# gatedriver_trafo_sma_compact_ACDC_ultra_.net
KiCad netlist of a schematic drawn in EAGLE
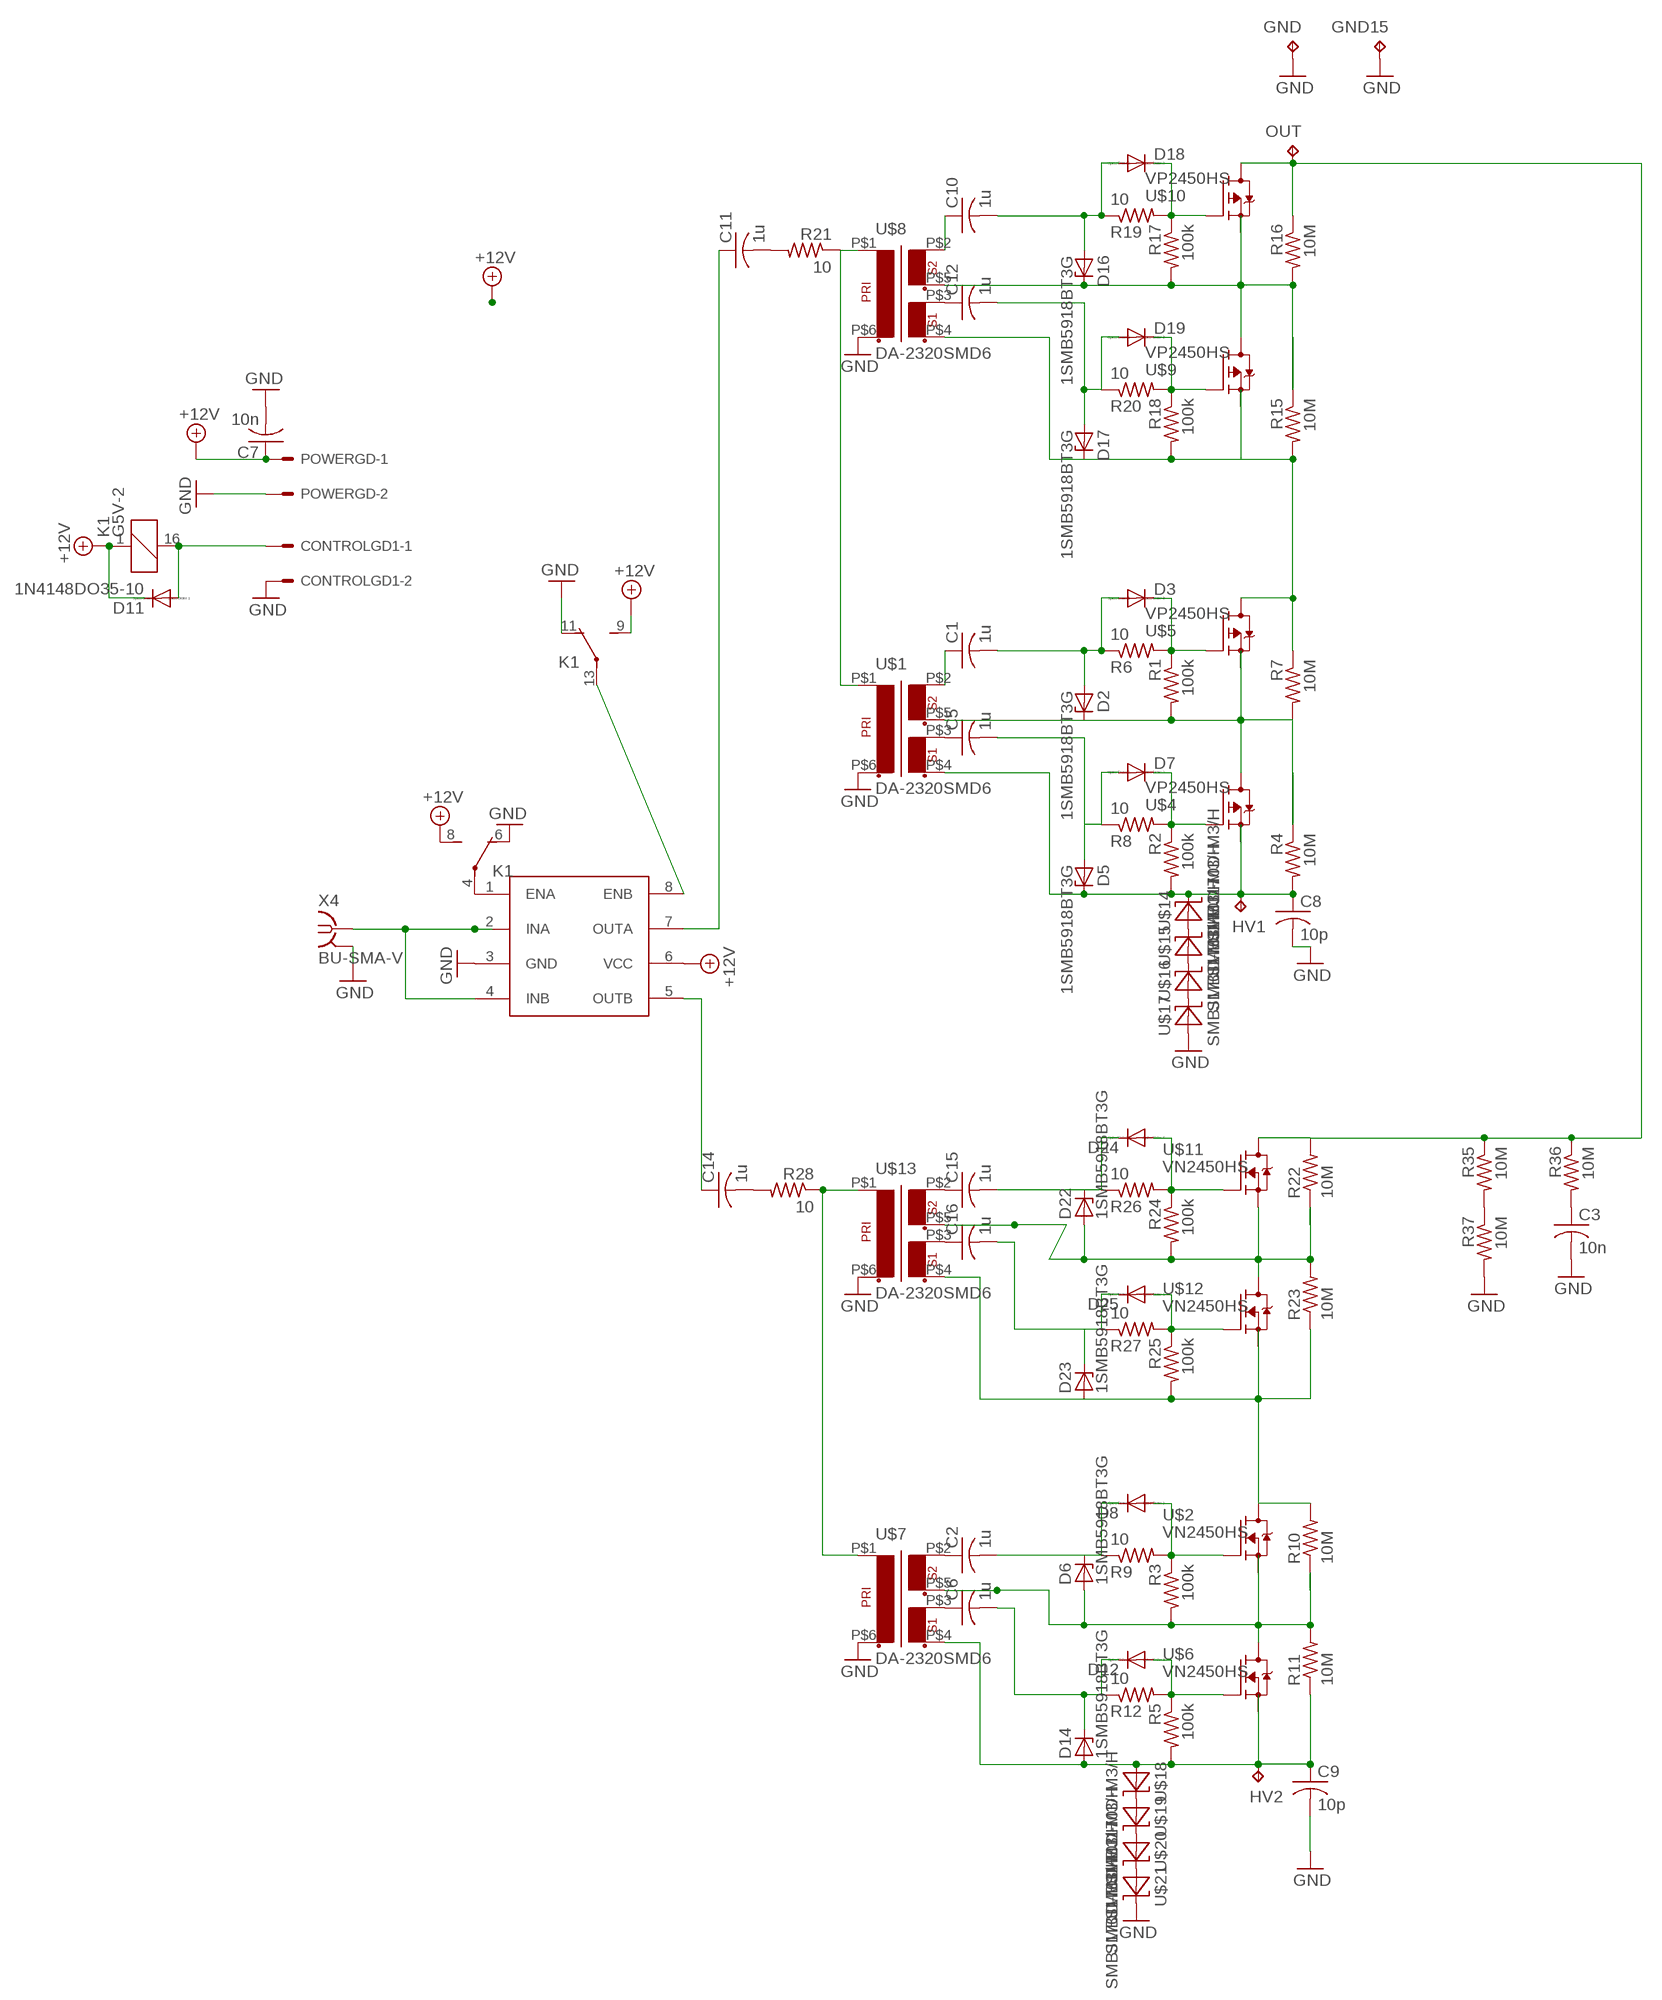
[diagram p0: schematic, sheet 1]

(export (version "E")
  (design (tool "Eeschema 10.0.6"))
  (components
    (comp (ref "C1")
      (value "1u")
      (footprint "eagle-import:C0805")
      (libsource (lib "eagle-import") (part "resistor_C-USC0805"))
    )
    (comp (ref "C2")
      (value "1u")
      (footprint "eagle-import:C0805")
      (libsource (lib "eagle-import") (part "resistor_C-USC0805"))
    )
    (comp (ref "C3")
      (value "10n")
      (footprint "eagle-import:C0805")
      (libsource (lib "eagle-import") (part "resistor_C-USC0805"))
    )
    (comp (ref "C5")
      (value "1u")
      (footprint "eagle-import:C0805")
      (libsource (lib "eagle-import") (part "resistor_C-USC0805"))
    )
    (comp (ref "C6")
      (value "1u")
      (footprint "eagle-import:C0805")
      (libsource (lib "eagle-import") (part "resistor_C-USC0805"))
    )
    (comp (ref "C7")
      (value "10n")
      (footprint "eagle-import:C050-030X075")
      (libsource (lib "eagle-import") (part "C-US050-030X075"))
    )
    (comp (ref "C8")
      (value "10p")
      (footprint "eagle-import:C102-064X133")
      (libsource (lib "eagle-import") (part "resistor_C-US102-064X133"))
    )
    (comp (ref "C9")
      (value "10p")
      (footprint "eagle-import:C102-064X133")
      (libsource (lib "eagle-import") (part "resistor_C-US102-064X133"))
    )
    (comp (ref "C10")
      (value "1u")
      (footprint "eagle-import:C0805")
      (libsource (lib "eagle-import") (part "resistor_C-USC0805"))
    )
    (comp (ref "C11")
      (value "1u")
      (footprint "eagle-import:C0805")
      (libsource (lib "eagle-import") (part "resistor_C-USC0805"))
    )
    (comp (ref "C12")
      (value "1u")
      (footprint "eagle-import:C0805")
      (libsource (lib "eagle-import") (part "resistor_C-USC0805"))
    )
    (comp (ref "C14")
      (value "1u")
      (footprint "eagle-import:C0805")
      (libsource (lib "eagle-import") (part "resistor_C-USC0805"))
    )
    (comp (ref "C15")
      (value "1u")
      (footprint "eagle-import:C0805")
      (libsource (lib "eagle-import") (part "resistor_C-USC0805"))
    )
    (comp (ref "C16")
      (value "1u")
      (footprint "eagle-import:C0805")
      (libsource (lib "eagle-import") (part "resistor_C-USC0805"))
    )
    (comp (ref "CONTROLGD1")
      (value "KK-156-2")
      (footprint "eagle-import:KK-156-2")
      (libsource (lib "eagle-import") (part "KK-156-2"))
    )
    (comp (ref "D2")
      (value "1SMB5918BT3G")
      (footprint "eagle-import:SMB")
      (libsource (lib "eagle-import") (part "ZENER-DIODESMB"))
    )
    (comp (ref "D3")
      (value "DIODE-SMB")
      (footprint "eagle-import:SMB")
      (libsource (lib "eagle-import") (part "DIODE-SMB"))
    )
    (comp (ref "D5")
      (value "1SMB5918BT3G")
      (footprint "eagle-import:SMB")
      (libsource (lib "eagle-import") (part "ZENER-DIODESMB"))
    )
    (comp (ref "D6")
      (value "1SMB5918BT3G")
      (footprint "eagle-import:SMB")
      (libsource (lib "eagle-import") (part "ZENER-DIODESMB"))
    )
    (comp (ref "D7")
      (value "DIODE-SMB")
      (footprint "eagle-import:SMB")
      (libsource (lib "eagle-import") (part "DIODE-SMB"))
    )
    (comp (ref "D8")
      (value "DIODE-SMB")
      (footprint "eagle-import:SMB")
      (libsource (lib "eagle-import") (part "DIODE-SMB"))
    )
    (comp (ref "D11")
      (value "1N4148DO35-10")
      (footprint "eagle-import:DO35-10")
      (libsource (lib "eagle-import") (part "1N4148DO35-10"))
    )
    (comp (ref "D12")
      (value "DIODE-SMB")
      (footprint "eagle-import:SMB")
      (libsource (lib "eagle-import") (part "DIODE-SMB"))
    )
    (comp (ref "D14")
      (value "1SMB5918BT3G")
      (footprint "eagle-import:SMB")
      (libsource (lib "eagle-import") (part "ZENER-DIODESMB"))
    )
    (comp (ref "D16")
      (value "1SMB5918BT3G")
      (footprint "eagle-import:SMB")
      (libsource (lib "eagle-import") (part "ZENER-DIODESMB"))
    )
    (comp (ref "D17")
      (value "1SMB5918BT3G")
      (footprint "eagle-import:SMB")
      (libsource (lib "eagle-import") (part "ZENER-DIODESMB"))
    )
    (comp (ref "D18")
      (value "DIODE-SMB")
      (footprint "eagle-import:SMB")
      (libsource (lib "eagle-import") (part "DIODE-SMB"))
    )
    (comp (ref "D19")
      (value "DIODE-SMB")
      (footprint "eagle-import:SMB")
      (libsource (lib "eagle-import") (part "DIODE-SMB"))
    )
    (comp (ref "D22")
      (value "1SMB5918BT3G")
      (footprint "eagle-import:SMB")
      (libsource (lib "eagle-import") (part "ZENER-DIODESMB"))
    )
    (comp (ref "D23")
      (value "1SMB5918BT3G")
      (footprint "eagle-import:SMB")
      (libsource (lib "eagle-import") (part "ZENER-DIODESMB"))
    )
    (comp (ref "D24")
      (value "DIODE-SMB")
      (footprint "eagle-import:SMB")
      (libsource (lib "eagle-import") (part "DIODE-SMB"))
    )
    (comp (ref "D25")
      (value "DIODE-SMB")
      (footprint "eagle-import:SMB")
      (libsource (lib "eagle-import") (part "DIODE-SMB"))
    )
    (comp (ref "GND")
      (value "TPPAD1-20Y")
      (footprint "eagle-import:P1-20Y")
      (libsource (lib "eagle-import") (part "TPPAD1-20Y"))
    )
    (comp (ref "GND15")
      (value "TPPAD1-20Y")
      (footprint "eagle-import:P1-20Y")
      (libsource (lib "eagle-import") (part "TPPAD1-20Y"))
    )
    (comp (ref "HV1")
      (value "TPPAD1-20Y")
      (footprint "eagle-import:P1-20Y")
      (libsource (lib "eagle-import") (part "TPPAD1-20Y"))
    )
    (comp (ref "HV2")
      (value "TPPAD1-20Y")
      (footprint "eagle-import:P1-20Y")
      (libsource (lib "eagle-import") (part "TPPAD1-20Y"))
    )
    (comp (ref "K1")
      (value "G5V-2")
      (footprint "eagle-import:G5V-2")
      (fields (field (name "MPN") "G5V-2 5DC"))
      (libsource (lib "eagle-import") (part "G5V-2"))
    )
    (comp (ref "OUT")
      (value "TPPAD1-20Y")
      (footprint "eagle-import:P1-20Y")
      (libsource (lib "eagle-import") (part "TPPAD1-20Y"))
    )
    (comp (ref "POWERGD")
      (value "KK-156-2")
      (footprint "eagle-import:KK-156-2")
      (libsource (lib "eagle-import") (part "KK-156-2"))
    )
    (comp (ref "R1")
      (value "100k")
      (footprint "eagle-import:R0805")
      (libsource (lib "eagle-import") (part "R-US_R0805"))
    )
    (comp (ref "R2")
      (value "100k")
      (footprint "eagle-import:R0805")
      (libsource (lib "eagle-import") (part "R-US_R0805"))
    )
    (comp (ref "R3")
      (value "100k")
      (footprint "eagle-import:R0805")
      (libsource (lib "eagle-import") (part "R-US_R0805"))
    )
    (comp (ref "R4")
      (value "10M")
      (footprint "eagle-import:R2512")
      (libsource (lib "eagle-import") (part "R-US_R2512"))
    )
    (comp (ref "R5")
      (value "100k")
      (footprint "eagle-import:R0805")
      (libsource (lib "eagle-import") (part "R-US_R0805"))
    )
    (comp (ref "R6")
      (value "10")
      (footprint "eagle-import:R0805")
      (libsource (lib "eagle-import") (part "R-US_R0805"))
    )
    (comp (ref "R7")
      (value "10M")
      (footprint "eagle-import:R2512")
      (libsource (lib "eagle-import") (part "R-US_R2512"))
    )
    (comp (ref "R8")
      (value "10")
      (footprint "eagle-import:R0805")
      (libsource (lib "eagle-import") (part "R-US_R0805"))
    )
    (comp (ref "R9")
      (value "10")
      (footprint "eagle-import:R0805")
      (libsource (lib "eagle-import") (part "R-US_R0805"))
    )
    (comp (ref "R10")
      (value "10M")
      (footprint "eagle-import:R2512")
      (libsource (lib "eagle-import") (part "R-US_R2512"))
    )
    (comp (ref "R11")
      (value "10M")
      (footprint "eagle-import:R2512")
      (libsource (lib "eagle-import") (part "R-US_R2512"))
    )
    (comp (ref "R12")
      (value "10")
      (footprint "eagle-import:R0805")
      (libsource (lib "eagle-import") (part "R-US_R0805"))
    )
    (comp (ref "R15")
      (value "10M")
      (footprint "eagle-import:R2512")
      (libsource (lib "eagle-import") (part "R-US_R2512"))
    )
    (comp (ref "R16")
      (value "10M")
      (footprint "eagle-import:R2512")
      (libsource (lib "eagle-import") (part "R-US_R2512"))
    )
    (comp (ref "R17")
      (value "100k")
      (footprint "eagle-import:R0805")
      (libsource (lib "eagle-import") (part "R-US_R0805"))
    )
    (comp (ref "R18")
      (value "100k")
      (footprint "eagle-import:R0805")
      (libsource (lib "eagle-import") (part "R-US_R0805"))
    )
    (comp (ref "R19")
      (value "10")
      (footprint "eagle-import:R0805")
      (libsource (lib "eagle-import") (part "R-US_R0805"))
    )
    (comp (ref "R20")
      (value "10")
      (footprint "eagle-import:R0805")
      (libsource (lib "eagle-import") (part "R-US_R0805"))
    )
    (comp (ref "R21")
      (value "10")
      (footprint "eagle-import:R0805")
      (libsource (lib "eagle-import") (part "R-US_R0805"))
    )
    (comp (ref "R22")
      (value "10M")
      (footprint "eagle-import:R2512")
      (libsource (lib "eagle-import") (part "R-US_R2512"))
    )
    (comp (ref "R23")
      (value "10M")
      (footprint "eagle-import:R2512")
      (libsource (lib "eagle-import") (part "R-US_R2512"))
    )
    (comp (ref "R24")
      (value "100k")
      (footprint "eagle-import:R0805")
      (libsource (lib "eagle-import") (part "R-US_R0805"))
    )
    (comp (ref "R25")
      (value "100k")
      (footprint "eagle-import:R0805")
      (libsource (lib "eagle-import") (part "R-US_R0805"))
    )
    (comp (ref "R26")
      (value "10")
      (footprint "eagle-import:R0805")
      (libsource (lib "eagle-import") (part "R-US_R0805"))
    )
    (comp (ref "R27")
      (value "10")
      (footprint "eagle-import:R0805")
      (libsource (lib "eagle-import") (part "R-US_R0805"))
    )
    (comp (ref "R28")
      (value "10")
      (footprint "eagle-import:R0805")
      (libsource (lib "eagle-import") (part "R-US_R0805"))
    )
    (comp (ref "R35")
      (value "10M")
      (footprint "eagle-import:R2512")
      (libsource (lib "eagle-import") (part "R-US_R2512"))
    )
    (comp (ref "R36")
      (value "10M")
      (footprint "eagle-import:R2512")
      (libsource (lib "eagle-import") (part "R-US_R2512"))
    )
    (comp (ref "R37")
      (value "10M")
      (footprint "eagle-import:R2512")
      (libsource (lib "eagle-import") (part "R-US_R2512"))
    )
    (comp (ref "U$1")
      (value "DA-2320SMD6")
      (footprint "eagle-import:SMD6")
      (libsource (lib "eagle-import") (part "DA-2320SMD6"))
    )
    (comp (ref "U$2")
      (value "VN2450HS")
      (footprint "eagle-import:SO89_HS")
      (libsource (lib "eagle-import") (part "VN2450HS"))
    )
    (comp (ref "U$3")
      (value "UCC27425")
      (footprint "eagle-import:DIL08")
      (libsource (lib "eagle-import") (part "UCC27425"))
    )
    (comp (ref "U$4")
      (value "VP2450HS")
      (footprint "eagle-import:SO89_HS")
      (libsource (lib "eagle-import") (part "VP2450HS"))
    )
    (comp (ref "U$5")
      (value "VP2450HS")
      (footprint "eagle-import:SO89_HS")
      (libsource (lib "eagle-import") (part "VP2450HS"))
    )
    (comp (ref "U$6")
      (value "VN2450HS")
      (footprint "eagle-import:SO89_HS")
      (libsource (lib "eagle-import") (part "VN2450HS"))
    )
    (comp (ref "U$7")
      (value "DA-2320SMD6")
      (footprint "eagle-import:SMD6")
      (libsource (lib "eagle-import") (part "DA-2320SMD6"))
    )
    (comp (ref "U$8")
      (value "DA-2320SMD6")
      (footprint "eagle-import:SMD6")
      (libsource (lib "eagle-import") (part "DA-2320SMD6"))
    )
    (comp (ref "U$9")
      (value "VP2450HS")
      (footprint "eagle-import:SO89_HS")
      (libsource (lib "eagle-import") (part "VP2450HS"))
    )
    (comp (ref "U$10")
      (value "VP2450HS")
      (footprint "eagle-import:SO89_HS")
      (libsource (lib "eagle-import") (part "VP2450HS"))
    )
    (comp (ref "U$11")
      (value "VN2450HS")
      (footprint "eagle-import:SO89_HS")
      (libsource (lib "eagle-import") (part "VN2450HS"))
    )
    (comp (ref "U$12")
      (value "VN2450HS")
      (footprint "eagle-import:SO89_HS")
      (libsource (lib "eagle-import") (part "VN2450HS"))
    )
    (comp (ref "U$13")
      (value "DA-2320SMD6")
      (footprint "eagle-import:SMD6")
      (libsource (lib "eagle-import") (part "DA-2320SMD6"))
    )
    (comp (ref "U$14")
      (value "SMBJ170D-M3/H")
      (footprint "eagle-import:DO214AA")
      (libsource (lib "eagle-import") (part "SMBJ170D-M3/H"))
    )
    (comp (ref "U$15")
      (value "SMBJ170D-M3/H")
      (footprint "eagle-import:DO214AA")
      (libsource (lib "eagle-import") (part "SMBJ170D-M3/H"))
    )
    (comp (ref "U$16")
      (value "SMBJ170D-M3/H")
      (footprint "eagle-import:DO214AA")
      (libsource (lib "eagle-import") (part "SMBJ170D-M3/H"))
    )
    (comp (ref "U$17")
      (value "SMBJ170D-M3/H")
      (footprint "eagle-import:DO214AA")
      (libsource (lib "eagle-import") (part "SMBJ170D-M3/H"))
    )
    (comp (ref "U$18")
      (value "SMBJ170D-M3/H")
      (footprint "eagle-import:DO214AA")
      (libsource (lib "eagle-import") (part "SMBJ170D-M3/H"))
    )
    (comp (ref "U$19")
      (value "SMBJ170D-M3/H")
      (footprint "eagle-import:DO214AA")
      (libsource (lib "eagle-import") (part "SMBJ170D-M3/H"))
    )
    (comp (ref "U$20")
      (value "SMBJ170D-M3/H")
      (footprint "eagle-import:DO214AA")
      (libsource (lib "eagle-import") (part "SMBJ170D-M3/H"))
    )
    (comp (ref "U$21")
      (value "SMBJ170D-M3/H")
      (footprint "eagle-import:DO214AA")
      (libsource (lib "eagle-import") (part "SMBJ170D-M3/H"))
    )
    (comp (ref "X4")
      (value "BU-SMA-V")
      (footprint "eagle-import:BU-SMA-V")
      (libsource (lib "eagle-import") (part "BU-SMA-V"))
    )
  )
  (nets
    (net (code "1") (name "+12V") (class "Default")
      (node (ref "C7") (pin "1") (pinfunction "1_1") (pintype "passive"))
      (node (ref "D11") (pin "C") (pinfunction "C_C") (pintype "passive"))
      (node (ref "K1") (pin "1") (pinfunction "1_1") (pintype "passive"))
      (node (ref "K1") (pin "8") (pinfunction "S_8") (pintype "passive"))
      (node (ref "K1") (pin "9") (pinfunction "S_9") (pintype "passive"))
      (node (ref "POWERGD") (pin "1") (pinfunction "S_1") (pintype "passive"))
      (node (ref "U$3") (pin "6") (pinfunction "VCC_6") (pintype "bidirectional"))
    )
    (net (code "2") (name "GND") (class "Default")
      (node (ref "C3") (pin "2") (pinfunction "2_2") (pintype "passive"))
      (node (ref "C7") (pin "2") (pinfunction "2_2") (pintype "passive"))
      (node (ref "C8") (pin "2") (pinfunction "2_2") (pintype "passive"))
      (node (ref "C9") (pin "2") (pinfunction "2_2") (pintype "passive"))
      (node (ref "CONTROLGD1") (pin "2") (pinfunction "S_2") (pintype "passive"))
      (node (ref "GND") (pin "TP") (pinfunction "TP_TP") (pintype "input"))
      (node (ref "GND15") (pin "TP") (pinfunction "TP_TP") (pintype "input"))
      (node (ref "K1") (pin "11") (pinfunction "O_11") (pintype "passive"))
      (node (ref "K1") (pin "6") (pinfunction "O_6") (pintype "passive"))
      (node (ref "POWERGD") (pin "2") (pinfunction "S_2") (pintype "passive"))
      (node (ref "R37") (pin "2") (pinfunction "2_2") (pintype "passive"))
      (node (ref "U$1") (pin "P$6") (pinfunction "2_P$6") (pintype "passive"))
      (node (ref "U$13") (pin "P$6") (pinfunction "2_P$6") (pintype "passive"))
      (node (ref "U$17") (pin "A") (pinfunction "A_A") (pintype "passive"))
      (node (ref "U$21") (pin "C") (pinfunction "C_C") (pintype "passive"))
      (node (ref "U$3") (pin "3") (pinfunction "GND_3") (pintype "bidirectional"))
      (node (ref "U$7") (pin "P$6") (pinfunction "2_P$6") (pintype "passive"))
      (node (ref "U$8") (pin "P$6") (pinfunction "2_P$6") (pintype "passive"))
      (node (ref "X4") (pin "2") (pinfunction "2_2") (pintype "passive"))
      (node (ref "X4") (pin "3") (pinfunction "2_3") (pintype "passive"))
      (node (ref "X4") (pin "4") (pinfunction "2_4") (pintype "passive"))
      (node (ref "X4") (pin "5") (pinfunction "2_5") (pintype "passive"))
    )
    (net (code "3") (name "Net-(C1-Pad2)") (class "Default")
      (node (ref "C1") (pin "2") (pinfunction "2_2") (pintype "passive"))
      (node (ref "D2") (pin "A") (pinfunction "A_A") (pintype "passive"))
      (node (ref "D3") (pin "A") (pinfunction "A_A") (pintype "passive"))
      (node (ref "R6") (pin "1") (pinfunction "1_1") (pintype "passive"))
    )
    (net (code "4") (name "Net-(C2-Pad2)") (class "Default")
      (node (ref "C2") (pin "2") (pinfunction "2_2") (pintype "passive"))
      (node (ref "D6") (pin "C") (pinfunction "C_C") (pintype "passive"))
      (node (ref "D8") (pin "C") (pinfunction "C_C") (pintype "passive"))
      (node (ref "R9") (pin "1") (pinfunction "1_1") (pintype "passive"))
    )
    (net (code "5") (name "Net-(C3-Pad1)") (class "Default")
      (node (ref "C3") (pin "1") (pinfunction "1_1") (pintype "passive"))
      (node (ref "R36") (pin "2") (pinfunction "2_2") (pintype "passive"))
    )
    (net (code "6") (name "Net-(C5-Pad2)") (class "Default")
      (node (ref "C5") (pin "2") (pinfunction "2_2") (pintype "passive"))
      (node (ref "D5") (pin "A") (pinfunction "A_A") (pintype "passive"))
      (node (ref "D7") (pin "A") (pinfunction "A_A") (pintype "passive"))
      (node (ref "R8") (pin "1") (pinfunction "1_1") (pintype "passive"))
    )
    (net (code "7") (name "Net-(C6-Pad2)") (class "Default")
      (node (ref "C6") (pin "2") (pinfunction "2_2") (pintype "passive"))
      (node (ref "D12") (pin "C") (pinfunction "C_C") (pintype "passive"))
      (node (ref "D14") (pin "C") (pinfunction "C_C") (pintype "passive"))
      (node (ref "R12") (pin "1") (pinfunction "1_1") (pintype "passive"))
    )
    (net (code "8") (name "Net-(C10-Pad2)") (class "Default")
      (node (ref "C10") (pin "2") (pinfunction "2_2") (pintype "passive"))
      (node (ref "D16") (pin "A") (pinfunction "A_A") (pintype "passive"))
      (node (ref "D18") (pin "A") (pinfunction "A_A") (pintype "passive"))
      (node (ref "R19") (pin "1") (pinfunction "1_1") (pintype "passive"))
    )
    (net (code "9") (name "Net-(C11-Pad2)") (class "Default")
      (node (ref "C11") (pin "2") (pinfunction "2_2") (pintype "passive"))
      (node (ref "R21") (pin "2") (pinfunction "2_2") (pintype "passive"))
    )
    (net (code "10") (name "Net-(C12-Pad2)") (class "Default")
      (node (ref "C12") (pin "2") (pinfunction "2_2") (pintype "passive"))
      (node (ref "D17") (pin "A") (pinfunction "A_A") (pintype "passive"))
      (node (ref "D19") (pin "A") (pinfunction "A_A") (pintype "passive"))
      (node (ref "R20") (pin "1") (pinfunction "1_1") (pintype "passive"))
    )
    (net (code "11") (name "Net-(C14-Pad2)") (class "Default")
      (node (ref "C14") (pin "2") (pinfunction "2_2") (pintype "passive"))
      (node (ref "R28") (pin "2") (pinfunction "2_2") (pintype "passive"))
    )
    (net (code "12") (name "Net-(C15-Pad2)") (class "Default")
      (node (ref "C15") (pin "2") (pinfunction "2_2") (pintype "passive"))
      (node (ref "D22") (pin "C") (pinfunction "C_C") (pintype "passive"))
      (node (ref "D24") (pin "C") (pinfunction "C_C") (pintype "passive"))
      (node (ref "R26") (pin "1") (pinfunction "1_1") (pintype "passive"))
    )
    (net (code "13") (name "Net-(C16-Pad2)") (class "Default")
      (node (ref "C16") (pin "2") (pinfunction "2_2") (pintype "passive"))
      (node (ref "D23") (pin "C") (pinfunction "C_C") (pintype "passive"))
      (node (ref "D25") (pin "C") (pinfunction "C_C") (pintype "passive"))
      (node (ref "R27") (pin "1") (pinfunction "1_1") (pintype "passive"))
    )
    (net (code "14") (name "Net-(CONTROLGD1A-S)") (class "Default")
      (node (ref "CONTROLGD1") (pin "1") (pinfunction "S_1") (pintype "passive"))
      (node (ref "D11") (pin "A") (pinfunction "A_A") (pintype "passive"))
      (node (ref "K1") (pin "16") (pinfunction "2_16") (pintype "passive"))
    )
    (net (code "15") (name "Net-(K1A-P)") (class "Default")
      (node (ref "K1") (pin "4") (pinfunction "P_4") (pintype "passive"))
      (node (ref "U$3") (pin "1") (pinfunction "ENA_1") (pintype "bidirectional"))
    )
    (net (code "16") (name "Net-(K1B-P)") (class "Default")
      (node (ref "K1") (pin "13") (pinfunction "P_13") (pintype "passive"))
      (node (ref "U$3") (pin "8") (pinfunction "ENB_8") (pintype "bidirectional"))
    )
    (net (code "17") (name "Net-(OUT-PadTP)") (class "Default")
      (node (ref "OUT") (pin "TP") (pinfunction "TP_TP") (pintype "input"))
      (node (ref "R16") (pin "1") (pinfunction "1_1") (pintype "passive"))
      (node (ref "R22") (pin "2") (pinfunction "2_2") (pintype "passive"))
      (node (ref "R35") (pin "1") (pinfunction "1_1") (pintype "passive"))
      (node (ref "R36") (pin "1") (pinfunction "1_1") (pintype "passive"))
      (node (ref "U$10") (pin "C") (pinfunction "D_C") (pintype "passive"))
      (node (ref "U$10") (pin "C@1") (pinfunction "D_C@1") (pintype "passive"))
      (node (ref "U$11") (pin "C") (pinfunction "D_C") (pintype "passive"))
      (node (ref "U$11") (pin "C@1") (pinfunction "D_C@1") (pintype "passive"))
    )
    (net (code "18") (name "Net-(R35-Pad2)") (class "Default")
      (node (ref "R35") (pin "2") (pinfunction "2_2") (pintype "passive"))
      (node (ref "R37") (pin "1") (pinfunction "1_1") (pintype "passive"))
    )
    (net (code "19") (name "Net-(U$1-1)") (class "Default")
      (node (ref "R21") (pin "1") (pinfunction "1_1") (pintype "passive"))
      (node (ref "U$1") (pin "P$1") (pinfunction "1_P$1") (pintype "passive"))
      (node (ref "U$8") (pin "P$1") (pinfunction "1_P$1") (pintype "passive"))
    )
    (net (code "20") (name "Net-(U$1-3)") (class "Default")
      (node (ref "C8") (pin "1") (pinfunction "1_1") (pintype "passive"))
      (node (ref "D5") (pin "C") (pinfunction "C_C") (pintype "passive"))
      (node (ref "HV1") (pin "TP") (pinfunction "TP_TP") (pintype "input"))
      (node (ref "R2") (pin "2") (pinfunction "2_2") (pintype "passive"))
      (node (ref "R4") (pin "2") (pinfunction "2_2") (pintype "passive"))
      (node (ref "U$1") (pin "P$4") (pinfunction "3_P$4") (pintype "passive"))
      (node (ref "U$14") (pin "C") (pinfunction "C_C") (pintype "passive"))
      (node (ref "U$4") (pin "E") (pinfunction "S_E") (pintype "passive"))
    )
    (net (code "21") (name "Net-(U$1-4)") (class "Default")
      (node (ref "C5") (pin "1") (pinfunction "1_1") (pintype "passive"))
      (node (ref "U$1") (pin "P$3") (pinfunction "4_P$3") (pintype "passive"))
    )
    (net (code "22") (name "Net-(U$1-5)") (class "Default")
      (node (ref "D2") (pin "C") (pinfunction "C_C") (pintype "passive"))
      (node (ref "R1") (pin "2") (pinfunction "2_2") (pintype "passive"))
      (node (ref "R4") (pin "1") (pinfunction "1_1") (pintype "passive"))
      (node (ref "R7") (pin "2") (pinfunction "2_2") (pintype "passive"))
      (node (ref "U$1") (pin "P$5") (pinfunction "5_P$5") (pintype "passive"))
      (node (ref "U$4") (pin "C") (pinfunction "D_C") (pintype "passive"))
      (node (ref "U$4") (pin "C@1") (pinfunction "D_C@1") (pintype "passive"))
      (node (ref "U$5") (pin "E") (pinfunction "S_E") (pintype "passive"))
    )
    (net (code "23") (name "Net-(U$1-6)") (class "Default")
      (node (ref "C1") (pin "1") (pinfunction "1_1") (pintype "passive"))
      (node (ref "U$1") (pin "P$2") (pinfunction "6_P$2") (pintype "passive"))
    )
    (net (code "24") (name "Net-(U$2-G)") (class "Default")
      (node (ref "D8") (pin "A") (pinfunction "A_A") (pintype "passive"))
      (node (ref "R3") (pin "1") (pinfunction "1_1") (pintype "passive"))
      (node (ref "R9") (pin "2") (pinfunction "2_2") (pintype "passive"))
      (node (ref "U$2") (pin "B") (pinfunction "G_B") (pintype "passive"))
    )
    (net (code "25") (name "Net-(U$2-S)") (class "Default")
      (node (ref "D6") (pin "A") (pinfunction "A_A") (pintype "passive"))
      (node (ref "R10") (pin "1") (pinfunction "1_1") (pintype "passive"))
      (node (ref "R11") (pin "2") (pinfunction "2_2") (pintype "passive"))
      (node (ref "R3") (pin "2") (pinfunction "2_2") (pintype "passive"))
      (node (ref "U$2") (pin "E") (pinfunction "S_E") (pintype "passive"))
      (node (ref "U$6") (pin "C") (pinfunction "D_C") (pintype "passive"))
      (node (ref "U$6") (pin "C@1") (pinfunction "D_C@1") (pintype "passive"))
      (node (ref "U$7") (pin "P$5") (pinfunction "5_P$5") (pintype "passive"))
    )
    (net (code "26") (name "Net-(U$3-INA)") (class "Default")
      (node (ref "U$3") (pin "2") (pinfunction "INA_2") (pintype "bidirectional"))
      (node (ref "U$3") (pin "4") (pinfunction "INB_4") (pintype "bidirectional"))
      (node (ref "X4") (pin "1") (pinfunction "1_1") (pintype "passive"))
    )
    (net (code "27") (name "Net-(U$3-OUTA)") (class "Default")
      (node (ref "C11") (pin "1") (pinfunction "1_1") (pintype "passive"))
      (node (ref "U$3") (pin "7") (pinfunction "OUTA_7") (pintype "bidirectional"))
    )
    (net (code "28") (name "Net-(U$3-OUTB)") (class "Default")
      (node (ref "C14") (pin "1") (pinfunction "1_1") (pintype "passive"))
      (node (ref "U$3") (pin "5") (pinfunction "OUTB_5") (pintype "bidirectional"))
    )
    (net (code "29") (name "Net-(U$4-G)") (class "Default")
      (node (ref "D7") (pin "C") (pinfunction "C_C") (pintype "passive"))
      (node (ref "R2") (pin "1") (pinfunction "1_1") (pintype "passive"))
      (node (ref "R8") (pin "2") (pinfunction "2_2") (pintype "passive"))
      (node (ref "U$4") (pin "B") (pinfunction "G_B") (pintype "passive"))
    )
    (net (code "30") (name "Net-(U$5-G)") (class "Default")
      (node (ref "D3") (pin "C") (pinfunction "C_C") (pintype "passive"))
      (node (ref "R1") (pin "1") (pinfunction "1_1") (pintype "passive"))
      (node (ref "R6") (pin "2") (pinfunction "2_2") (pintype "passive"))
      (node (ref "U$5") (pin "B") (pinfunction "G_B") (pintype "passive"))
    )
    (net (code "31") (name "Net-(U$6-G)") (class "Default")
      (node (ref "D12") (pin "A") (pinfunction "A_A") (pintype "passive"))
      (node (ref "R12") (pin "2") (pinfunction "2_2") (pintype "passive"))
      (node (ref "R5") (pin "1") (pinfunction "1_1") (pintype "passive"))
      (node (ref "U$6") (pin "B") (pinfunction "G_B") (pintype "passive"))
    )
    (net (code "32") (name "Net-(U$6-S)") (class "Default")
      (node (ref "C9") (pin "1") (pinfunction "1_1") (pintype "passive"))
      (node (ref "D14") (pin "A") (pinfunction "A_A") (pintype "passive"))
      (node (ref "HV2") (pin "TP") (pinfunction "TP_TP") (pintype "input"))
      (node (ref "R11") (pin "1") (pinfunction "1_1") (pintype "passive"))
      (node (ref "R5") (pin "2") (pinfunction "2_2") (pintype "passive"))
      (node (ref "U$18") (pin "A") (pinfunction "A_A") (pintype "passive"))
      (node (ref "U$6") (pin "E") (pinfunction "S_E") (pintype "passive"))
      (node (ref "U$7") (pin "P$4") (pinfunction "3_P$4") (pintype "passive"))
    )
    (net (code "33") (name "Net-(U$7-4)") (class "Default")
      (node (ref "C6") (pin "1") (pinfunction "1_1") (pintype "passive"))
      (node (ref "U$7") (pin "P$3") (pinfunction "4_P$3") (pintype "passive"))
    )
    (net (code "34") (name "Net-(U$7-6)") (class "Default")
      (node (ref "C2") (pin "1") (pinfunction "1_1") (pintype "passive"))
      (node (ref "U$7") (pin "P$2") (pinfunction "6_P$2") (pintype "passive"))
    )
    (net (code "35") (name "Net-(U$8-3)") (class "Default")
      (node (ref "D17") (pin "C") (pinfunction "C_C") (pintype "passive"))
      (node (ref "R15") (pin "2") (pinfunction "2_2") (pintype "passive"))
      (node (ref "R18") (pin "2") (pinfunction "2_2") (pintype "passive"))
      (node (ref "R7") (pin "1") (pinfunction "1_1") (pintype "passive"))
      (node (ref "U$5") (pin "C") (pinfunction "D_C") (pintype "passive"))
      (node (ref "U$5") (pin "C@1") (pinfunction "D_C@1") (pintype "passive"))
      (node (ref "U$8") (pin "P$4") (pinfunction "3_P$4") (pintype "passive"))
      (node (ref "U$9") (pin "E") (pinfunction "S_E") (pintype "passive"))
    )
    (net (code "36") (name "Net-(U$8-4)") (class "Default")
      (node (ref "C12") (pin "1") (pinfunction "1_1") (pintype "passive"))
      (node (ref "U$8") (pin "P$3") (pinfunction "4_P$3") (pintype "passive"))
    )
    (net (code "37") (name "Net-(U$8-6)") (class "Default")
      (node (ref "C10") (pin "1") (pinfunction "1_1") (pintype "passive"))
      (node (ref "U$8") (pin "P$2") (pinfunction "6_P$2") (pintype "passive"))
    )
    (net (code "38") (name "Net-(U$9-G)") (class "Default")
      (node (ref "D19") (pin "C") (pinfunction "C_C") (pintype "passive"))
      (node (ref "R18") (pin "1") (pinfunction "1_1") (pintype "passive"))
      (node (ref "R20") (pin "2") (pinfunction "2_2") (pintype "passive"))
      (node (ref "U$9") (pin "B") (pinfunction "G_B") (pintype "passive"))
    )
    (net (code "39") (name "Net-(U$10-G)") (class "Default")
      (node (ref "D18") (pin "C") (pinfunction "C_C") (pintype "passive"))
      (node (ref "R17") (pin "1") (pinfunction "1_1") (pintype "passive"))
      (node (ref "R19") (pin "2") (pinfunction "2_2") (pintype "passive"))
      (node (ref "U$10") (pin "B") (pinfunction "G_B") (pintype "passive"))
    )
    (net (code "40") (name "Net-(U$10-S)") (class "Default")
      (node (ref "D16") (pin "C") (pinfunction "C_C") (pintype "passive"))
      (node (ref "R15") (pin "1") (pinfunction "1_1") (pintype "passive"))
      (node (ref "R16") (pin "2") (pinfunction "2_2") (pintype "passive"))
      (node (ref "R17") (pin "2") (pinfunction "2_2") (pintype "passive"))
      (node (ref "U$10") (pin "E") (pinfunction "S_E") (pintype "passive"))
      (node (ref "U$8") (pin "P$5") (pinfunction "5_P$5") (pintype "passive"))
      (node (ref "U$9") (pin "C") (pinfunction "D_C") (pintype "passive"))
      (node (ref "U$9") (pin "C@1") (pinfunction "D_C@1") (pintype "passive"))
    )
    (net (code "41") (name "Net-(U$11-G)") (class "Default")
      (node (ref "D24") (pin "A") (pinfunction "A_A") (pintype "passive"))
      (node (ref "R24") (pin "1") (pinfunction "1_1") (pintype "passive"))
      (node (ref "R26") (pin "2") (pinfunction "2_2") (pintype "passive"))
      (node (ref "U$11") (pin "B") (pinfunction "G_B") (pintype "passive"))
    )
    (net (code "42") (name "Net-(U$11-S)") (class "Default")
      (node (ref "D22") (pin "A") (pinfunction "A_A") (pintype "passive"))
      (node (ref "R22") (pin "1") (pinfunction "1_1") (pintype "passive"))
      (node (ref "R23") (pin "2") (pinfunction "2_2") (pintype "passive"))
      (node (ref "R24") (pin "2") (pinfunction "2_2") (pintype "passive"))
      (node (ref "U$11") (pin "E") (pinfunction "S_E") (pintype "passive"))
      (node (ref "U$12") (pin "C") (pinfunction "D_C") (pintype "passive"))
      (node (ref "U$12") (pin "C@1") (pinfunction "D_C@1") (pintype "passive"))
      (node (ref "U$13") (pin "P$5") (pinfunction "5_P$5") (pintype "passive"))
    )
    (net (code "43") (name "Net-(U$12-G)") (class "Default")
      (node (ref "D25") (pin "A") (pinfunction "A_A") (pintype "passive"))
      (node (ref "R25") (pin "1") (pinfunction "1_1") (pintype "passive"))
      (node (ref "R27") (pin "2") (pinfunction "2_2") (pintype "passive"))
      (node (ref "U$12") (pin "B") (pinfunction "G_B") (pintype "passive"))
    )
    (net (code "44") (name "Net-(U$12-S)") (class "Default")
      (node (ref "D23") (pin "A") (pinfunction "A_A") (pintype "passive"))
      (node (ref "R10") (pin "2") (pinfunction "2_2") (pintype "passive"))
      (node (ref "R23") (pin "1") (pinfunction "1_1") (pintype "passive"))
      (node (ref "R25") (pin "2") (pinfunction "2_2") (pintype "passive"))
      (node (ref "U$12") (pin "E") (pinfunction "S_E") (pintype "passive"))
      (node (ref "U$13") (pin "P$4") (pinfunction "3_P$4") (pintype "passive"))
      (node (ref "U$2") (pin "C") (pinfunction "D_C") (pintype "passive"))
      (node (ref "U$2") (pin "C@1") (pinfunction "D_C@1") (pintype "passive"))
    )
    (net (code "45") (name "Net-(U$13-1)") (class "Default")
      (node (ref "R28") (pin "1") (pinfunction "1_1") (pintype "passive"))
      (node (ref "U$13") (pin "P$1") (pinfunction "1_P$1") (pintype "passive"))
      (node (ref "U$7") (pin "P$1") (pinfunction "1_P$1") (pintype "passive"))
    )
    (net (code "46") (name "Net-(U$13-4)") (class "Default")
      (node (ref "C16") (pin "1") (pinfunction "1_1") (pintype "passive"))
      (node (ref "U$13") (pin "P$3") (pinfunction "4_P$3") (pintype "passive"))
    )
    (net (code "47") (name "Net-(U$13-6)") (class "Default")
      (node (ref "C15") (pin "1") (pinfunction "1_1") (pintype "passive"))
      (node (ref "U$13") (pin "P$2") (pinfunction "6_P$2") (pintype "passive"))
    )
    (net (code "48") (name "Net-(U$14-PadA)") (class "Default")
      (node (ref "U$14") (pin "A") (pinfunction "A_A") (pintype "passive"))
      (node (ref "U$15") (pin "C") (pinfunction "C_C") (pintype "passive"))
    )
    (net (code "49") (name "Net-(U$15-PadA)") (class "Default")
      (node (ref "U$15") (pin "A") (pinfunction "A_A") (pintype "passive"))
      (node (ref "U$16") (pin "C") (pinfunction "C_C") (pintype "passive"))
    )
    (net (code "50") (name "Net-(U$16-PadA)") (class "Default")
      (node (ref "U$16") (pin "A") (pinfunction "A_A") (pintype "passive"))
      (node (ref "U$17") (pin "C") (pinfunction "C_C") (pintype "passive"))
    )
    (net (code "51") (name "Net-(U$18-PadC)") (class "Default")
      (node (ref "U$18") (pin "C") (pinfunction "C_C") (pintype "passive"))
      (node (ref "U$19") (pin "A") (pinfunction "A_A") (pintype "passive"))
    )
    (net (code "52") (name "Net-(U$19-PadC)") (class "Default")
      (node (ref "U$19") (pin "C") (pinfunction "C_C") (pintype "passive"))
      (node (ref "U$20") (pin "A") (pinfunction "A_A") (pintype "passive"))
    )
    (net (code "53") (name "Net-(U$20-PadC)") (class "Default")
      (node (ref "U$20") (pin "C") (pinfunction "C_C") (pintype "passive"))
      (node (ref "U$21") (pin "A") (pinfunction "A_A") (pintype "passive"))
    )
  )
)
